# debug_interface.net
KiCad netlist of a schematic drawn in Altium Designer
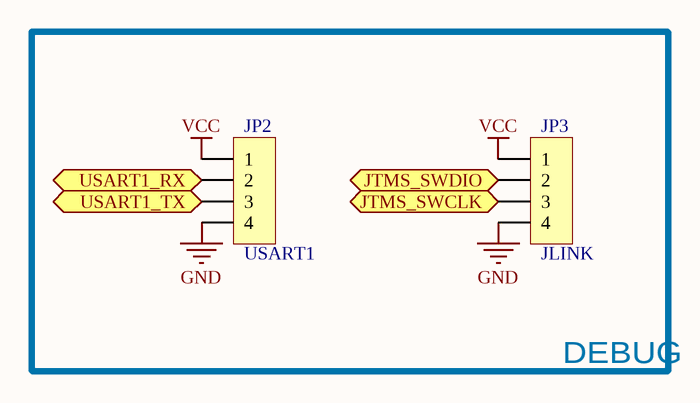
[diagram p0: debug_interface.SchDoc]

(export (version "E")
  (design (tool "Eeschema 10.0.6"))
  (components
    (comp (ref "JP2")
      (value "USART1")
      (footprint "MX 1.25-LS-4P")
      (description "4P接插件")
      (fields (field (name "版权归属") "源创客"))
      (libsource (lib "4.2   - 接插件-脚距1.25") (part "Header 4"))
    )
    (comp (ref "JP3")
      (value "JLINK")
      (footprint "MX 1.25-LS-4P")
      (description "4P接插件")
      (fields (field (name "版权归属") "源创客"))
      (libsource (lib "4.2   - 接插件-脚距1.25") (part "Header 4"))
    )
  )
  (nets
    (net (code "1") (name "/JTMS_SWCLK") (class "Default")
      (node (ref "JP3") (pin "3") (pinfunction "3_3") (pintype "passive"))
    )
    (net (code "2") (name "/JTMS_SWDIO") (class "Default")
      (node (ref "JP3") (pin "2") (pinfunction "2_2") (pintype "passive"))
    )
    (net (code "3") (name "/USART1_RX") (class "Default")
      (node (ref "JP2") (pin "2") (pinfunction "2_2") (pintype "passive"))
    )
    (net (code "4") (name "/USART1_TX") (class "Default")
      (node (ref "JP2") (pin "3") (pinfunction "3_3") (pintype "passive"))
    )
    (net (code "5") (name "GND") (class "Default")
      (node (ref "JP2") (pin "4") (pinfunction "4_4") (pintype "passive"))
      (node (ref "JP3") (pin "4") (pinfunction "4_4") (pintype "passive"))
    )
    (net (code "6") (name "VCC") (class "Default")
      (node (ref "JP2") (pin "1") (pinfunction "1_1") (pintype "passive"))
      (node (ref "JP3") (pin "1") (pinfunction "1_1") (pintype "passive"))
    )
  )
)
